# BTSM_Power_v1.net
KiCad netlist of a schematic drawn in Altium Designer
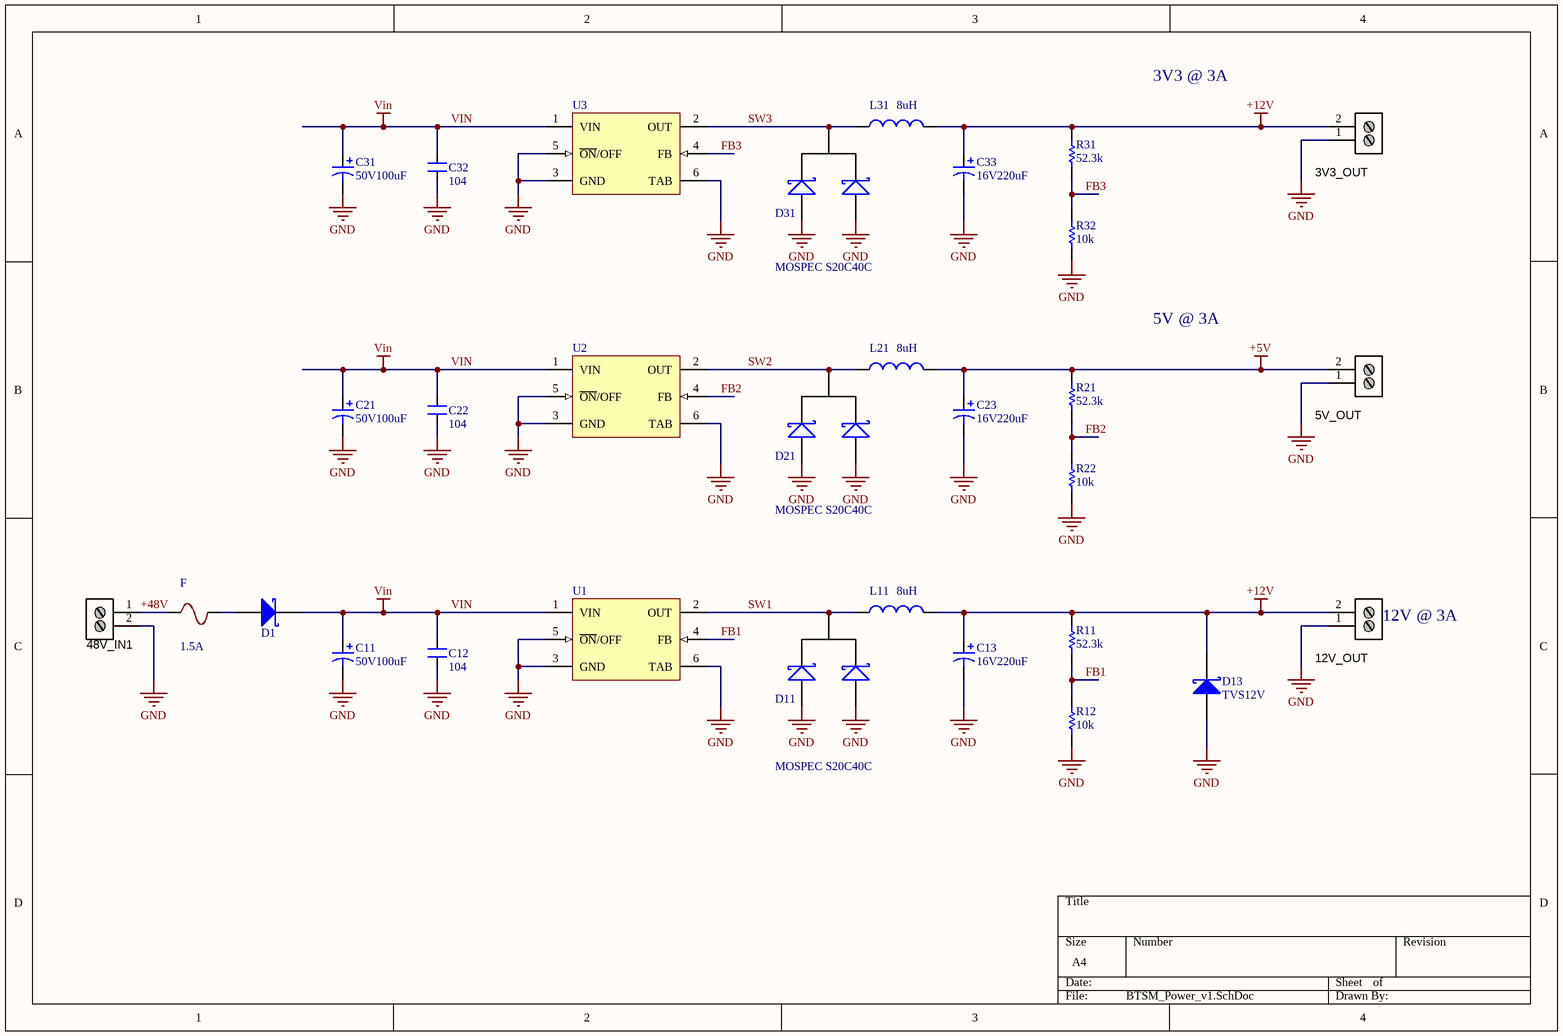
[diagram p0: BTSM_Power_v1.SchDoc]

(export (version "E")
  (design (tool "Eeschema 10.0.6"))
  (components
    (comp (ref "3V3_OUT")
      (value "Stackable ScrewTerm")
      (footprint "2P_PCB_ScrewTerm_200mil")
      (description "Terminal Block Screw Type THT 2-Position 3.81mm pitch")
      (libsource (lib "") (part "2P_ScrewTerm_90S_3.81MM_1"))
    )
    (comp (ref "5V_OUT")
      (value "Stackable ScrewTerm")
      (footprint "2P_PCB_ScrewTerm_200mil")
      (description "Terminal Block Screw Type THT 2-Position 3.81mm pitch")
      (libsource (lib "") (part "2P_ScrewTerm_90S_3.81MM_1"))
    )
    (comp (ref "12V_OUT")
      (value "Stackable ScrewTerm")
      (footprint "2P_PCB_ScrewTerm_200mil")
      (description "Terminal Block Screw Type THT 2-Position 3.81mm pitch")
      (libsource (lib "") (part "2P_ScrewTerm_90S_3.81MM_1"))
    )
    (comp (ref "48V_IN1")
      (value "Stackable ScrewTerm")
      (footprint "2P_PCB_ScrewTerm_200mil")
      (description "Terminal Block Screw Type THT 2-Position 3.81mm pitch")
      (libsource (lib "PBL - Connectors") (part "2P_ScrewTerm_90S_3.81MM"))
    )
    (comp (ref "C11")
      (value "50V100uF")
      (footprint "CAP 3.8mm")
      (fields (field (name "Comment") "Cap"))
      (libsource (lib "Tuan") (part "Cap"))
    )
    (comp (ref "C12")
      (value "104")
      (footprint "CAPC1608N")
      (fields (field (name "Comment") "CAP NP"))
      (libsource (lib "Tuan") (part "CAP NP"))
    )
    (comp (ref "C13")
      (value "16V220uF")
      (footprint "CAP 3.8mm")
      (fields (field (name "Comment") "Cap"))
      (libsource (lib "Tuan") (part "Cap"))
    )
    (comp (ref "C21")
      (value "50V100uF")
      (footprint "CAP 3.8mm")
      (fields (field (name "Comment") "Cap"))
      (libsource (lib "Tuan") (part "Cap"))
    )
    (comp (ref "C22")
      (value "104")
      (footprint "CAPC1608N")
      (fields (field (name "Comment") "CAP NP"))
      (libsource (lib "Tuan") (part "CAP NP"))
    )
    (comp (ref "C23")
      (value "16V220uF")
      (footprint "CAP 3.8mm")
      (fields (field (name "Comment") "Cap"))
      (libsource (lib "Tuan") (part "Cap"))
    )
    (comp (ref "C31")
      (value "50V100uF")
      (footprint "CAP 3.8mm")
      (fields (field (name "Comment") "Cap"))
      (libsource (lib "Tuan") (part "Cap"))
    )
    (comp (ref "C32")
      (value "104")
      (footprint "CAPC1608N")
      (fields (field (name "Comment") "CAP NP"))
      (libsource (lib "Tuan") (part "CAP NP"))
    )
    (comp (ref "C33")
      (value "16V220uF")
      (footprint "CAP 3.8mm")
      (fields (field (name "Comment") "Cap"))
      (libsource (lib "Tuan") (part "Cap"))
    )
    (comp (ref "D1") (value "SS14") (footprint "Diode 3A") (libsource (lib "Tuan") (part "Diode Schottky")))
    (comp (ref "D11")
      (value "MOSPEC S20C40C")
      (footprint "TO-220")
      (libsource (lib "Tuan") (part "Diode x2"))
    )
    (comp (ref "D13")
      (value "TVS12V")
      (footprint "DO-214AA")
      (libsource (lib "Tuan") (part "Diode Schottky"))
    )
    (comp (ref "D21")
      (value "MOSPEC S20C40C")
      (footprint "TO-220")
      (libsource (lib "Tuan") (part "Diode x2"))
    )
    (comp (ref "D31")
      (value "MOSPEC S20C40C")
      (footprint "TO-220")
      (libsource (lib "Tuan") (part "Diode x2"))
    )
    (comp (ref "F") (value "1.5A") (footprint "FUSE_SR-5-BK") (libsource (lib "Tuan") (part "Fuse")))
    (comp (ref "L11")
      (value "8uH")
      (footprint "Toroid")
      (fields (field (name "Comment") "Inductor"))
      (libsource (lib "Tuan") (part "Inductor"))
    )
    (comp (ref "L21")
      (value "8uH")
      (footprint "Toroid")
      (fields (field (name "Comment") "Inductor"))
      (libsource (lib "Tuan") (part "Inductor"))
    )
    (comp (ref "L31")
      (value "8uH")
      (footprint "Toroid")
      (fields (field (name "Comment") "Inductor"))
      (libsource (lib "Tuan") (part "Inductor"))
    )
    (comp (ref "R11")
      (value "52.3k")
      (footprint "RESC2012N")
      (fields (field (name "Comment") "Res"))
      (libsource (lib "Tuan") (part "Res"))
    )
    (comp (ref "R12")
      (value "10k")
      (footprint "RESC2012N")
      (fields (field (name "Comment") "Res"))
      (libsource (lib "Tuan") (part "Res"))
    )
    (comp (ref "R21")
      (value "52.3k")
      (footprint "RESC2012N")
      (fields (field (name "Comment") "Res"))
      (libsource (lib "Tuan") (part "Res"))
    )
    (comp (ref "R22")
      (value "10k")
      (footprint "RESC2012N")
      (fields (field (name "Comment") "Res"))
      (libsource (lib "Tuan") (part "Res"))
    )
    (comp (ref "R31")
      (value "52.3k")
      (footprint "RESC2012N")
      (fields (field (name "Comment") "Res"))
      (libsource (lib "Tuan") (part "Res"))
    )
    (comp (ref "R32")
      (value "10k")
      (footprint "RESC2012N")
      (fields (field (name "Comment") "Res"))
      (libsource (lib "Tuan") (part "Res"))
    )
    (comp (ref "U1")
      (value "LM2596S-ADJ")
      (footprint "TS5B_N")
      (description "SIMPLE SWITCHER Power Converter 150 KHz 3A Step-Down Voltage Regulator")
      (fields
        (field (name "MANUFACTURER") "National Semiconductor")
        (field (name "DIGIKEYPARTNUMBER") "LM2596S-ADJ-ND")
        (field (name "PUBLISHER") "Altium Limited")
      )
      (libsource (lib "NSC Switcher") (part "LM2596S-ADJ"))
    )
    (comp (ref "U2")
      (value "LM2596S-ADJ")
      (footprint "TS5B_N")
      (description "SIMPLE SWITCHER Power Converter 150 KHz 3A Step-Down Voltage Regulator")
      (fields
        (field (name "MANUFACTURER") "National Semiconductor")
        (field (name "DIGIKEYPARTNUMBER") "LM2596S-ADJ-ND")
        (field (name "PUBLISHER") "Altium Limited")
      )
      (libsource (lib "NSC Switcher") (part "LM2596S-ADJ"))
    )
    (comp (ref "U3")
      (value "LM2596S-ADJ")
      (footprint "TS5B_N")
      (description "SIMPLE SWITCHER Power Converter 150 KHz 3A Step-Down Voltage Regulator")
      (fields
        (field (name "MANUFACTURER") "National Semiconductor")
        (field (name "DIGIKEYPARTNUMBER") "LM2596S-ADJ-ND")
        (field (name "PUBLISHER") "Altium Limited")
      )
      (libsource (lib "NSC Switcher") (part "LM2596S-ADJ"))
    )
  )
  (nets
    (net (code "1") (name "+5V") (class "Default")
      (node (ref "5V_OUT") (pin "2") (pinfunction "2_2") (pintype "passive"))
      (node (ref "C23") (pin "1") (pinfunction "1_1") (pintype "passive"))
      (node (ref "L21") (pin "2") (pinfunction "2_2") (pintype "passive"))
      (node (ref "R21") (pin "2") (pinfunction "2_2") (pintype "passive"))
    )
    (net (code "2") (name "+12V") (class "Default")
      (node (ref "12V_OUT") (pin "2") (pinfunction "2_2") (pintype "passive"))
      (node (ref "3V3_OUT") (pin "2") (pinfunction "2_2") (pintype "passive"))
      (node (ref "C13") (pin "1") (pinfunction "1_1") (pintype "passive"))
      (node (ref "C33") (pin "1") (pinfunction "1_1") (pintype "passive"))
      (node (ref "D13") (pin "2") (pinfunction "K_2") (pintype "passive"))
      (node (ref "L11") (pin "2") (pinfunction "2_2") (pintype "passive"))
      (node (ref "L31") (pin "2") (pinfunction "2_2") (pintype "passive"))
      (node (ref "R11") (pin "2") (pinfunction "2_2") (pintype "passive"))
      (node (ref "R31") (pin "2") (pinfunction "2_2") (pintype "passive"))
    )
    (net (code "3") (name "/+48V") (class "Default")
      (node (ref "48V_IN1") (pin "1") (pinfunction "1_1") (pintype "passive"))
      (node (ref "F") (pin "2") (pinfunction "2_2") (pintype "passive"))
    )
    (net (code "4") (name "/FB1") (class "Default")
      (node (ref "R11") (pin "1") (pinfunction "1_1") (pintype "passive"))
      (node (ref "R12") (pin "2") (pinfunction "2_2") (pintype "passive"))
      (node (ref "U1") (pin "4") (pinfunction "FB_4") (pintype "input"))
    )
    (net (code "5") (name "/FB2") (class "Default")
      (node (ref "R21") (pin "1") (pinfunction "1_1") (pintype "passive"))
      (node (ref "R22") (pin "2") (pinfunction "2_2") (pintype "passive"))
      (node (ref "U2") (pin "4") (pinfunction "FB_4") (pintype "input"))
    )
    (net (code "6") (name "/FB3") (class "Default")
      (node (ref "R31") (pin "1") (pinfunction "1_1") (pintype "passive"))
      (node (ref "R32") (pin "2") (pinfunction "2_2") (pintype "passive"))
      (node (ref "U3") (pin "4") (pinfunction "FB_4") (pintype "input"))
    )
    (net (code "7") (name "/SW1") (class "Default")
      (node (ref "D11") (pin "2") (pinfunction "A2_2") (pintype "passive"))
      (node (ref "L11") (pin "1") (pinfunction "1_1") (pintype "passive"))
      (node (ref "U1") (pin "2") (pinfunction "OUT_2") (pintype "power_in"))
    )
    (net (code "8") (name "/SW2") (class "Default")
      (node (ref "D21") (pin "2") (pinfunction "A2_2") (pintype "passive"))
      (node (ref "L21") (pin "1") (pinfunction "1_1") (pintype "passive"))
      (node (ref "U2") (pin "2") (pinfunction "OUT_2") (pintype "power_in"))
    )
    (net (code "9") (name "/SW3") (class "Default")
      (node (ref "D31") (pin "2") (pinfunction "A2_2") (pintype "passive"))
      (node (ref "L31") (pin "1") (pinfunction "1_1") (pintype "passive"))
      (node (ref "U3") (pin "2") (pinfunction "OUT_2") (pintype "power_in"))
    )
    (net (code "10") (name "GND") (class "Default")
      (node (ref "12V_OUT") (pin "1") (pinfunction "1_1") (pintype "passive"))
      (node (ref "3V3_OUT") (pin "1") (pinfunction "1_1") (pintype "passive"))
      (node (ref "48V_IN1") (pin "2") (pinfunction "2_2") (pintype "passive"))
      (node (ref "5V_OUT") (pin "1") (pinfunction "1_1") (pintype "passive"))
      (node (ref "C11") (pin "2") (pinfunction "2_2") (pintype "passive"))
      (node (ref "C12") (pin "1") (pinfunction "1_1") (pintype "passive"))
      (node (ref "C13") (pin "2") (pinfunction "2_2") (pintype "passive"))
      (node (ref "C21") (pin "2") (pinfunction "2_2") (pintype "passive"))
      (node (ref "C22") (pin "1") (pinfunction "1_1") (pintype "passive"))
      (node (ref "C23") (pin "2") (pinfunction "2_2") (pintype "passive"))
      (node (ref "C31") (pin "2") (pinfunction "2_2") (pintype "passive"))
      (node (ref "C32") (pin "1") (pinfunction "1_1") (pintype "passive"))
      (node (ref "C33") (pin "2") (pinfunction "2_2") (pintype "passive"))
      (node (ref "D11") (pin "1") (pinfunction "A1_1") (pintype "passive"))
      (node (ref "D11") (pin "3") (pinfunction "K_3") (pintype "passive"))
      (node (ref "D13") (pin "1") (pinfunction "A_1") (pintype "passive"))
      (node (ref "D21") (pin "1") (pinfunction "A1_1") (pintype "passive"))
      (node (ref "D21") (pin "3") (pinfunction "K_3") (pintype "passive"))
      (node (ref "D31") (pin "1") (pinfunction "A1_1") (pintype "passive"))
      (node (ref "D31") (pin "3") (pinfunction "K_3") (pintype "passive"))
      (node (ref "R12") (pin "1") (pinfunction "1_1") (pintype "passive"))
      (node (ref "R22") (pin "1") (pinfunction "1_1") (pintype "passive"))
      (node (ref "R32") (pin "1") (pinfunction "1_1") (pintype "passive"))
      (node (ref "U1") (pin "3") (pinfunction "GND_3") (pintype "power_in"))
      (node (ref "U1") (pin "5") (pinfunction "~{ON}/OFF_5") (pintype "input"))
      (node (ref "U1") (pin "6") (pinfunction "TAB_6") (pintype "power_in"))
      (node (ref "U2") (pin "3") (pinfunction "GND_3") (pintype "power_in"))
      (node (ref "U2") (pin "5") (pinfunction "~{ON}/OFF_5") (pintype "input"))
      (node (ref "U2") (pin "6") (pinfunction "TAB_6") (pintype "power_in"))
      (node (ref "U3") (pin "3") (pinfunction "GND_3") (pintype "power_in"))
      (node (ref "U3") (pin "5") (pinfunction "~{ON}/OFF_5") (pintype "input"))
      (node (ref "U3") (pin "6") (pinfunction "TAB_6") (pintype "power_in"))
    )
    (net (code "11") (name "Net-(D1-A)") (class "Default")
      (node (ref "D1") (pin "1") (pinfunction "A_1") (pintype "passive"))
      (node (ref "F") (pin "1") (pinfunction "1_1") (pintype "passive"))
    )
    (net (code "12") (name "Vin") (class "Default")
      (node (ref "C11") (pin "1") (pinfunction "1_1") (pintype "passive"))
      (node (ref "C12") (pin "2") (pinfunction "2_2") (pintype "passive"))
      (node (ref "C21") (pin "1") (pinfunction "1_1") (pintype "passive"))
      (node (ref "C22") (pin "2") (pinfunction "2_2") (pintype "passive"))
      (node (ref "C31") (pin "1") (pinfunction "1_1") (pintype "passive"))
      (node (ref "C32") (pin "2") (pinfunction "2_2") (pintype "passive"))
      (node (ref "D1") (pin "2") (pinfunction "K_2") (pintype "passive"))
      (node (ref "U1") (pin "1") (pinfunction "VIN_1") (pintype "power_in"))
      (node (ref "U2") (pin "1") (pinfunction "VIN_1") (pintype "power_in"))
      (node (ref "U3") (pin "1") (pinfunction "VIN_1") (pintype "power_in"))
    )
  )
)
